# 4_5in_touch_LED_driver.net
KiCad netlist of a schematic drawn in EAGLE
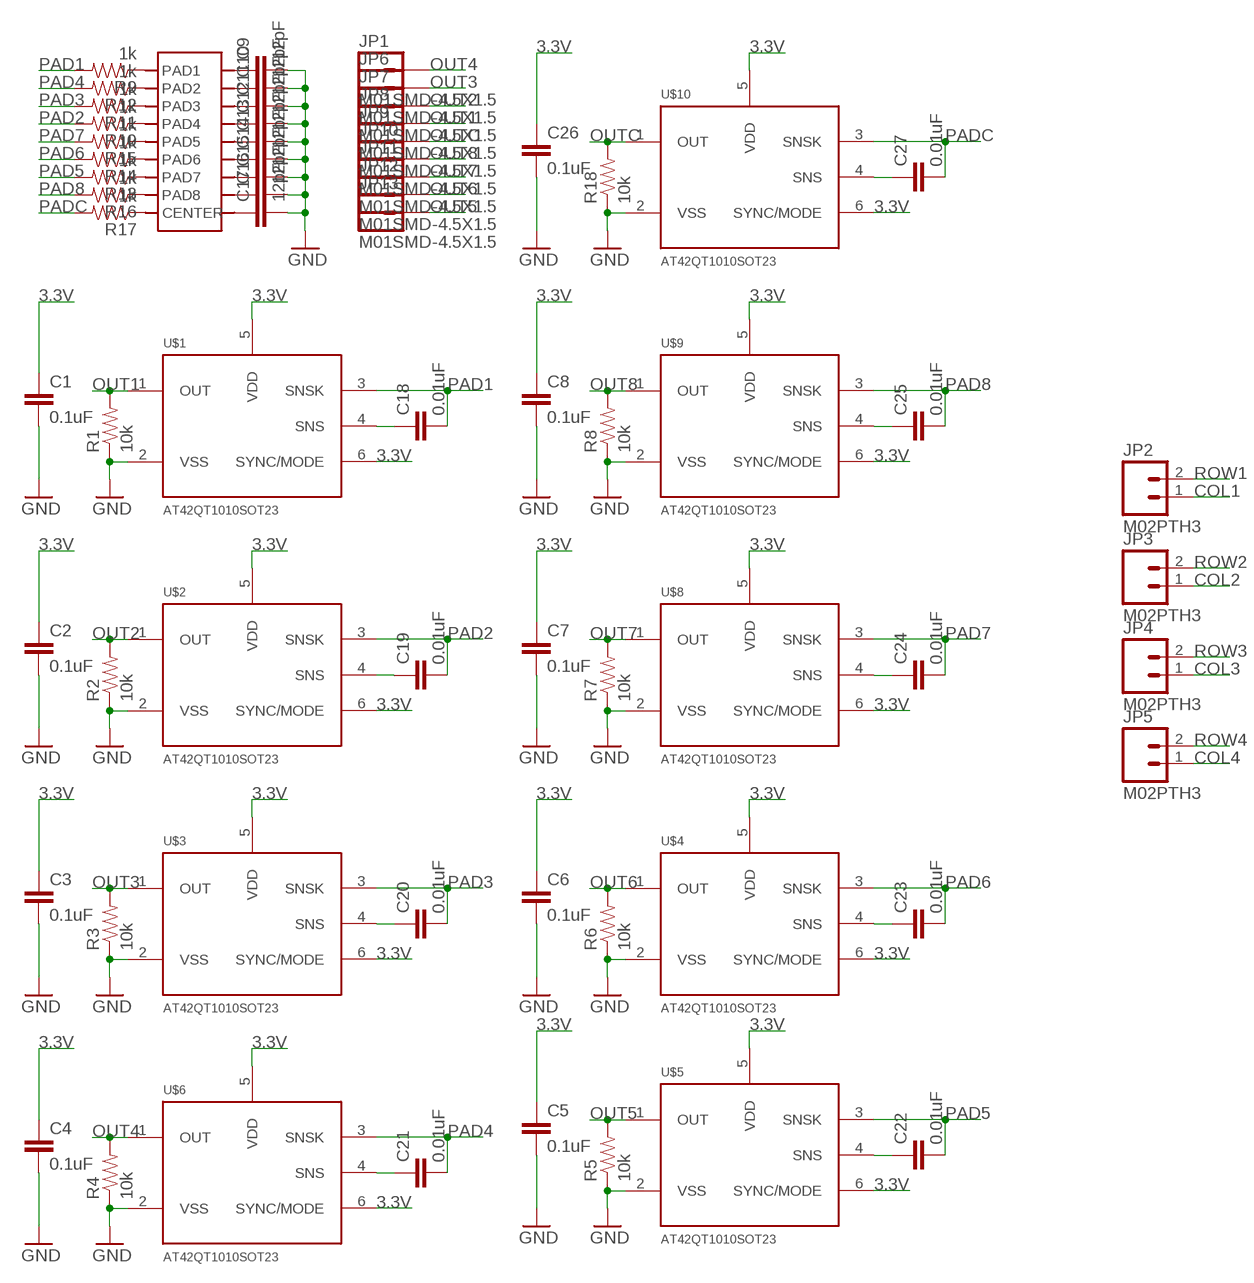
[diagram p0: schematic, sheet 1]

(export (version "E")
  (design (tool "Eeschema 10.0.6"))
  (components
    (comp (ref "C1")
      (value "0.1uF")
      (footprint "eagle-import:0603-CAP")
      (libsource (lib "eagle-import") (part "0.1UF-25V-5%(0603)"))
    )
    (comp (ref "C2")
      (value "0.1uF")
      (footprint "eagle-import:0603-CAP")
      (libsource (lib "eagle-import") (part "0.1UF-25V-5%(0603)"))
    )
    (comp (ref "C3")
      (value "0.1uF")
      (footprint "eagle-import:0603-CAP")
      (libsource (lib "eagle-import") (part "0.1UF-25V-5%(0603)"))
    )
    (comp (ref "C4")
      (value "0.1uF")
      (footprint "eagle-import:0603-CAP")
      (libsource (lib "eagle-import") (part "0.1UF-25V-5%(0603)"))
    )
    (comp (ref "C5")
      (value "0.1uF")
      (footprint "eagle-import:0603-CAP")
      (libsource (lib "eagle-import") (part "0.1UF-25V-5%(0603)"))
    )
    (comp (ref "C6")
      (value "0.1uF")
      (footprint "eagle-import:0603-CAP")
      (libsource (lib "eagle-import") (part "0.1UF-25V-5%(0603)"))
    )
    (comp (ref "C7")
      (value "0.1uF")
      (footprint "eagle-import:0603-CAP")
      (libsource (lib "eagle-import") (part "0.1UF-25V-5%(0603)"))
    )
    (comp (ref "C8")
      (value "0.1uF")
      (footprint "eagle-import:0603-CAP")
      (libsource (lib "eagle-import") (part "0.1UF-25V-5%(0603)"))
    )
    (comp (ref "C9")
      (value "12pF")
      (footprint "eagle-import:0805")
      (libsource (lib "eagle-import") (part "CAP0805"))
    )
    (comp (ref "C10")
      (value "12pF")
      (footprint "eagle-import:0805")
      (libsource (lib "eagle-import") (part "CAP0805"))
    )
    (comp (ref "C11")
      (value "12pF")
      (footprint "eagle-import:0805")
      (libsource (lib "eagle-import") (part "CAP0805"))
    )
    (comp (ref "C12")
      (value "12pF")
      (footprint "eagle-import:0805")
      (libsource (lib "eagle-import") (part "CAP0805"))
    )
    (comp (ref "C13")
      (value "12pF")
      (footprint "eagle-import:0805")
      (libsource (lib "eagle-import") (part "CAP0805"))
    )
    (comp (ref "C14")
      (value "12pF")
      (footprint "eagle-import:0805")
      (libsource (lib "eagle-import") (part "CAP0805"))
    )
    (comp (ref "C15")
      (value "12pF")
      (footprint "eagle-import:0805")
      (libsource (lib "eagle-import") (part "CAP0805"))
    )
    (comp (ref "C16")
      (value "12pF")
      (footprint "eagle-import:0805")
      (libsource (lib "eagle-import") (part "CAP0805"))
    )
    (comp (ref "C17")
      (value "12pF")
      (footprint "eagle-import:0805")
      (libsource (lib "eagle-import") (part "CAP0805"))
    )
    (comp (ref "C18")
      (value "0.01uF")
      (footprint "eagle-import:0805")
      (libsource (lib "eagle-import") (part "CAP0805"))
    )
    (comp (ref "C19")
      (value "0.01uF")
      (footprint "eagle-import:0805")
      (libsource (lib "eagle-import") (part "CAP0805"))
    )
    (comp (ref "C20")
      (value "0.01uF")
      (footprint "eagle-import:0805")
      (libsource (lib "eagle-import") (part "CAP0805"))
    )
    (comp (ref "C21")
      (value "0.01uF")
      (footprint "eagle-import:0805")
      (libsource (lib "eagle-import") (part "CAP0805"))
    )
    (comp (ref "C22")
      (value "0.01uF")
      (footprint "eagle-import:0805")
      (libsource (lib "eagle-import") (part "CAP0805"))
    )
    (comp (ref "C23")
      (value "0.01uF")
      (footprint "eagle-import:0805")
      (libsource (lib "eagle-import") (part "CAP0805"))
    )
    (comp (ref "C24")
      (value "0.01uF")
      (footprint "eagle-import:0805")
      (libsource (lib "eagle-import") (part "CAP0805"))
    )
    (comp (ref "C25")
      (value "0.01uF")
      (footprint "eagle-import:0805")
      (libsource (lib "eagle-import") (part "CAP0805"))
    )
    (comp (ref "C26")
      (value "0.1uF")
      (footprint "eagle-import:0603-CAP")
      (libsource (lib "eagle-import") (part "0.1UF-25V-5%(0603)"))
    )
    (comp (ref "C27")
      (value "0.01uF")
      (footprint "eagle-import:0805")
      (libsource (lib "eagle-import") (part "CAP0805"))
    )
    (comp (ref "JP1")
      (value "M01SMD-4.5X1.5")
      (footprint "eagle-import:PAD-1.5X4.5")
      (libsource (lib "eagle-import") (part "M01SMD-4.5X1.5"))
    )
    (comp (ref "JP2")
      (value "M02PTH3")
      (footprint "eagle-import:1X02_LONGPADS")
      (libsource (lib "eagle-import") (part "M02PTH3"))
    )
    (comp (ref "JP3")
      (value "M02PTH3")
      (footprint "eagle-import:1X02_LONGPADS")
      (libsource (lib "eagle-import") (part "M02PTH3"))
    )
    (comp (ref "JP4")
      (value "M02PTH3")
      (footprint "eagle-import:1X02_LONGPADS")
      (libsource (lib "eagle-import") (part "M02PTH3"))
    )
    (comp (ref "JP5")
      (value "M02PTH3")
      (footprint "eagle-import:1X02_LONGPADS")
      (libsource (lib "eagle-import") (part "M02PTH3"))
    )
    (comp (ref "JP6")
      (value "M01SMD-4.5X1.5")
      (footprint "eagle-import:PAD-1.5X4.5")
      (libsource (lib "eagle-import") (part "M01SMD-4.5X1.5"))
    )
    (comp (ref "JP7")
      (value "M01SMD-4.5X1.5")
      (footprint "eagle-import:PAD-1.5X4.5")
      (libsource (lib "eagle-import") (part "M01SMD-4.5X1.5"))
    )
    (comp (ref "JP8")
      (value "M01SMD-4.5X1.5")
      (footprint "eagle-import:PAD-1.5X4.5")
      (libsource (lib "eagle-import") (part "M01SMD-4.5X1.5"))
    )
    (comp (ref "JP9")
      (value "M01SMD-4.5X1.5")
      (footprint "eagle-import:PAD-1.5X4.5")
      (libsource (lib "eagle-import") (part "M01SMD-4.5X1.5"))
    )
    (comp (ref "JP10")
      (value "M01SMD-4.5X1.5")
      (footprint "eagle-import:PAD-1.5X4.5")
      (libsource (lib "eagle-import") (part "M01SMD-4.5X1.5"))
    )
    (comp (ref "JP11")
      (value "M01SMD-4.5X1.5")
      (footprint "eagle-import:PAD-1.5X4.5")
      (libsource (lib "eagle-import") (part "M01SMD-4.5X1.5"))
    )
    (comp (ref "JP12")
      (value "M01SMD-4.5X1.5")
      (footprint "eagle-import:PAD-1.5X4.5")
      (libsource (lib "eagle-import") (part "M01SMD-4.5X1.5"))
    )
    (comp (ref "JP13")
      (value "M01SMD-4.5X1.5")
      (footprint "eagle-import:PAD-1.5X4.5")
      (libsource (lib "eagle-import") (part "M01SMD-4.5X1.5"))
    )
    (comp (ref "R1")
      (value "10k")
      (footprint "eagle-import:0603-RES")
      (libsource (lib "eagle-import") (part "RESISTOR0603"))
    )
    (comp (ref "R2")
      (value "10k")
      (footprint "eagle-import:0603-RES")
      (libsource (lib "eagle-import") (part "RESISTOR0603"))
    )
    (comp (ref "R3")
      (value "10k")
      (footprint "eagle-import:0603-RES")
      (libsource (lib "eagle-import") (part "RESISTOR0603"))
    )
    (comp (ref "R4")
      (value "10k")
      (footprint "eagle-import:0603-RES")
      (libsource (lib "eagle-import") (part "RESISTOR0603"))
    )
    (comp (ref "R5")
      (value "10k")
      (footprint "eagle-import:0603-RES")
      (libsource (lib "eagle-import") (part "RESISTOR0603"))
    )
    (comp (ref "R6")
      (value "10k")
      (footprint "eagle-import:0603-RES")
      (libsource (lib "eagle-import") (part "RESISTOR0603"))
    )
    (comp (ref "R7")
      (value "10k")
      (footprint "eagle-import:0603-RES")
      (libsource (lib "eagle-import") (part "RESISTOR0603"))
    )
    (comp (ref "R8")
      (value "10k")
      (footprint "eagle-import:0603-RES")
      (libsource (lib "eagle-import") (part "RESISTOR0603"))
    )
    (comp (ref "R9")
      (value "1k")
      (footprint "eagle-import:0603-RES")
      (libsource (lib "eagle-import") (part "RESISTOR0603"))
    )
    (comp (ref "R10")
      (value "1k")
      (footprint "eagle-import:0603-RES")
      (libsource (lib "eagle-import") (part "RESISTOR0603"))
    )
    (comp (ref "R11")
      (value "1k")
      (footprint "eagle-import:0603-RES")
      (libsource (lib "eagle-import") (part "RESISTOR0603"))
    )
    (comp (ref "R12")
      (value "1k")
      (footprint "eagle-import:0603-RES")
      (libsource (lib "eagle-import") (part "RESISTOR0603"))
    )
    (comp (ref "R13")
      (value "1k")
      (footprint "eagle-import:0603-RES")
      (libsource (lib "eagle-import") (part "RESISTOR0603"))
    )
    (comp (ref "R14")
      (value "1k")
      (footprint "eagle-import:0603-RES")
      (libsource (lib "eagle-import") (part "RESISTOR0603"))
    )
    (comp (ref "R15")
      (value "1k")
      (footprint "eagle-import:0603-RES")
      (libsource (lib "eagle-import") (part "RESISTOR0603"))
    )
    (comp (ref "R16")
      (value "1k")
      (footprint "eagle-import:0603-RES")
      (libsource (lib "eagle-import") (part "RESISTOR0603"))
    )
    (comp (ref "R17")
      (value "1k")
      (footprint "eagle-import:0603-RES")
      (libsource (lib "eagle-import") (part "RESISTOR0603"))
    )
    (comp (ref "R18")
      (value "10k")
      (footprint "eagle-import:0603-RES")
      (libsource (lib "eagle-import") (part "RESISTOR0603"))
    )
    (comp (ref "U$1")
      (value "AT42QT1010SOT23")
      (footprint "eagle-import:SOT23-6")
      (libsource (lib "eagle-import") (part "AT42QT1010SOT23"))
    )
    (comp (ref "U$2")
      (value "AT42QT1010SOT23")
      (footprint "eagle-import:SOT23-6")
      (libsource (lib "eagle-import") (part "AT42QT1010SOT23"))
    )
    (comp (ref "U$3")
      (value "AT42QT1010SOT23")
      (footprint "eagle-import:SOT23-6")
      (libsource (lib "eagle-import") (part "AT42QT1010SOT23"))
    )
    (comp (ref "U$4")
      (value "AT42QT1010SOT23")
      (footprint "eagle-import:SOT23-6")
      (libsource (lib "eagle-import") (part "AT42QT1010SOT23"))
    )
    (comp (ref "U$5")
      (value "AT42QT1010SOT23")
      (footprint "eagle-import:SOT23-6")
      (libsource (lib "eagle-import") (part "AT42QT1010SOT23"))
    )
    (comp (ref "U$6")
      (value "AT42QT1010SOT23")
      (footprint "eagle-import:SOT23-6")
      (libsource (lib "eagle-import") (part "AT42QT1010SOT23"))
    )
    (comp (ref "U$7")
      (value "9_PAD_TOUCH4IN")
      (footprint "eagle-import:4IN_TOUCH_PAD")
      (libsource (lib "eagle-import") (part "9_PAD_TOUCH4IN"))
    )
    (comp (ref "U$8")
      (value "AT42QT1010SOT23")
      (footprint "eagle-import:SOT23-6")
      (libsource (lib "eagle-import") (part "AT42QT1010SOT23"))
    )
    (comp (ref "U$9")
      (value "AT42QT1010SOT23")
      (footprint "eagle-import:SOT23-6")
      (libsource (lib "eagle-import") (part "AT42QT1010SOT23"))
    )
    (comp (ref "U$10")
      (value "AT42QT1010SOT23")
      (footprint "eagle-import:SOT23-6")
      (libsource (lib "eagle-import") (part "AT42QT1010SOT23"))
    )
  )
  (nets
    (net (code "1") (name "/3.3V") (class "Default")
      (node (ref "C1") (pin "1") (pinfunction "1_1") (pintype "passive"))
      (node (ref "C2") (pin "1") (pinfunction "1_1") (pintype "passive"))
      (node (ref "C26") (pin "1") (pinfunction "1_1") (pintype "passive"))
      (node (ref "C3") (pin "1") (pinfunction "1_1") (pintype "passive"))
      (node (ref "C4") (pin "1") (pinfunction "1_1") (pintype "passive"))
      (node (ref "C5") (pin "1") (pinfunction "1_1") (pintype "passive"))
      (node (ref "C6") (pin "1") (pinfunction "1_1") (pintype "passive"))
      (node (ref "C7") (pin "1") (pinfunction "1_1") (pintype "passive"))
      (node (ref "C8") (pin "1") (pinfunction "1_1") (pintype "passive"))
      (node (ref "U$1") (pin "5") (pinfunction "VDD_5") (pintype "bidirectional"))
      (node (ref "U$1") (pin "6") (pinfunction "SYNC/MODE_6") (pintype "bidirectional"))
      (node (ref "U$10") (pin "5") (pinfunction "VDD_5") (pintype "bidirectional"))
      (node (ref "U$10") (pin "6") (pinfunction "SYNC/MODE_6") (pintype "bidirectional"))
      (node (ref "U$2") (pin "5") (pinfunction "VDD_5") (pintype "bidirectional"))
      (node (ref "U$2") (pin "6") (pinfunction "SYNC/MODE_6") (pintype "bidirectional"))
      (node (ref "U$3") (pin "5") (pinfunction "VDD_5") (pintype "bidirectional"))
      (node (ref "U$3") (pin "6") (pinfunction "SYNC/MODE_6") (pintype "bidirectional"))
      (node (ref "U$4") (pin "5") (pinfunction "VDD_5") (pintype "bidirectional"))
      (node (ref "U$4") (pin "6") (pinfunction "SYNC/MODE_6") (pintype "bidirectional"))
      (node (ref "U$5") (pin "5") (pinfunction "VDD_5") (pintype "bidirectional"))
      (node (ref "U$5") (pin "6") (pinfunction "SYNC/MODE_6") (pintype "bidirectional"))
      (node (ref "U$6") (pin "5") (pinfunction "VDD_5") (pintype "bidirectional"))
      (node (ref "U$6") (pin "6") (pinfunction "SYNC/MODE_6") (pintype "bidirectional"))
      (node (ref "U$8") (pin "5") (pinfunction "VDD_5") (pintype "bidirectional"))
      (node (ref "U$8") (pin "6") (pinfunction "SYNC/MODE_6") (pintype "bidirectional"))
      (node (ref "U$9") (pin "5") (pinfunction "VDD_5") (pintype "bidirectional"))
      (node (ref "U$9") (pin "6") (pinfunction "SYNC/MODE_6") (pintype "bidirectional"))
    )
    (net (code "2") (name "/COL1") (class "Default")
      (node (ref "JP2") (pin "1") (pinfunction "1_1") (pintype "passive"))
    )
    (net (code "3") (name "/COL2") (class "Default")
      (node (ref "JP3") (pin "1") (pinfunction "1_1") (pintype "passive"))
    )
    (net (code "4") (name "/COL3") (class "Default")
      (node (ref "JP4") (pin "1") (pinfunction "1_1") (pintype "passive"))
    )
    (net (code "5") (name "/COL4") (class "Default")
      (node (ref "JP5") (pin "1") (pinfunction "1_1") (pintype "passive"))
    )
    (net (code "6") (name "/OUT1") (class "Default")
      (node (ref "JP8") (pin "P$1") (pinfunction "1_P$1") (pintype "passive"))
      (node (ref "R1") (pin "2") (pinfunction "2_2") (pintype "passive"))
      (node (ref "U$1") (pin "1") (pinfunction "OUT_1") (pintype "bidirectional"))
    )
    (net (code "7") (name "/OUT2") (class "Default")
      (node (ref "JP7") (pin "P$1") (pinfunction "1_P$1") (pintype "passive"))
      (node (ref "R2") (pin "2") (pinfunction "2_2") (pintype "passive"))
      (node (ref "U$2") (pin "1") (pinfunction "OUT_1") (pintype "bidirectional"))
    )
    (net (code "8") (name "/OUT3") (class "Default")
      (node (ref "JP6") (pin "P$1") (pinfunction "1_P$1") (pintype "passive"))
      (node (ref "R3") (pin "2") (pinfunction "2_2") (pintype "passive"))
      (node (ref "U$3") (pin "1") (pinfunction "OUT_1") (pintype "bidirectional"))
    )
    (net (code "9") (name "/OUT4") (class "Default")
      (node (ref "JP1") (pin "P$1") (pinfunction "1_P$1") (pintype "passive"))
      (node (ref "R4") (pin "2") (pinfunction "2_2") (pintype "passive"))
      (node (ref "U$6") (pin "1") (pinfunction "OUT_1") (pintype "bidirectional"))
    )
    (net (code "10") (name "/OUT5") (class "Default")
      (node (ref "JP13") (pin "P$1") (pinfunction "1_P$1") (pintype "passive"))
      (node (ref "R5") (pin "2") (pinfunction "2_2") (pintype "passive"))
      (node (ref "U$5") (pin "1") (pinfunction "OUT_1") (pintype "bidirectional"))
    )
    (net (code "11") (name "/OUT6") (class "Default")
      (node (ref "JP12") (pin "P$1") (pinfunction "1_P$1") (pintype "passive"))
      (node (ref "R6") (pin "2") (pinfunction "2_2") (pintype "passive"))
      (node (ref "U$4") (pin "1") (pinfunction "OUT_1") (pintype "bidirectional"))
    )
    (net (code "12") (name "/OUT7") (class "Default")
      (node (ref "JP11") (pin "P$1") (pinfunction "1_P$1") (pintype "passive"))
      (node (ref "R7") (pin "2") (pinfunction "2_2") (pintype "passive"))
      (node (ref "U$8") (pin "1") (pinfunction "OUT_1") (pintype "bidirectional"))
    )
    (net (code "13") (name "/OUT8") (class "Default")
      (node (ref "JP10") (pin "P$1") (pinfunction "1_P$1") (pintype "passive"))
      (node (ref "R8") (pin "2") (pinfunction "2_2") (pintype "passive"))
      (node (ref "U$9") (pin "1") (pinfunction "OUT_1") (pintype "bidirectional"))
    )
    (net (code "14") (name "/OUTC") (class "Default")
      (node (ref "JP9") (pin "P$1") (pinfunction "1_P$1") (pintype "passive"))
      (node (ref "R18") (pin "2") (pinfunction "2_2") (pintype "passive"))
      (node (ref "U$10") (pin "1") (pinfunction "OUT_1") (pintype "bidirectional"))
    )
    (net (code "15") (name "/PAD1") (class "Default")
      (node (ref "C18") (pin "2") (pinfunction "2_2") (pintype "passive"))
      (node (ref "R9") (pin "2") (pinfunction "2_2") (pintype "passive"))
      (node (ref "U$1") (pin "3") (pinfunction "SNSK_3") (pintype "bidirectional"))
    )
    (net (code "16") (name "/PAD2") (class "Default")
      (node (ref "C19") (pin "2") (pinfunction "2_2") (pintype "passive"))
      (node (ref "R10") (pin "2") (pinfunction "2_2") (pintype "passive"))
      (node (ref "U$2") (pin "3") (pinfunction "SNSK_3") (pintype "bidirectional"))
    )
    (net (code "17") (name "/PAD3") (class "Default")
      (node (ref "C20") (pin "2") (pinfunction "2_2") (pintype "passive"))
      (node (ref "R11") (pin "2") (pinfunction "2_2") (pintype "passive"))
      (node (ref "U$3") (pin "3") (pinfunction "SNSK_3") (pintype "bidirectional"))
    )
    (net (code "18") (name "/PAD4") (class "Default")
      (node (ref "C21") (pin "2") (pinfunction "2_2") (pintype "passive"))
      (node (ref "R12") (pin "2") (pinfunction "2_2") (pintype "passive"))
      (node (ref "U$6") (pin "3") (pinfunction "SNSK_3") (pintype "bidirectional"))
    )
    (net (code "19") (name "/PAD5") (class "Default")
      (node (ref "C22") (pin "2") (pinfunction "2_2") (pintype "passive"))
      (node (ref "R13") (pin "2") (pinfunction "2_2") (pintype "passive"))
      (node (ref "U$5") (pin "3") (pinfunction "SNSK_3") (pintype "bidirectional"))
    )
    (net (code "20") (name "/PAD6") (class "Default")
      (node (ref "C23") (pin "2") (pinfunction "2_2") (pintype "passive"))
      (node (ref "R14") (pin "2") (pinfunction "2_2") (pintype "passive"))
      (node (ref "U$4") (pin "3") (pinfunction "SNSK_3") (pintype "bidirectional"))
    )
    (net (code "21") (name "/PAD7") (class "Default")
      (node (ref "C24") (pin "2") (pinfunction "2_2") (pintype "passive"))
      (node (ref "R15") (pin "2") (pinfunction "2_2") (pintype "passive"))
      (node (ref "U$8") (pin "3") (pinfunction "SNSK_3") (pintype "bidirectional"))
    )
    (net (code "22") (name "/PAD8") (class "Default")
      (node (ref "C25") (pin "2") (pinfunction "2_2") (pintype "passive"))
      (node (ref "R16") (pin "2") (pinfunction "2_2") (pintype "passive"))
      (node (ref "U$9") (pin "3") (pinfunction "SNSK_3") (pintype "bidirectional"))
    )
    (net (code "23") (name "/PADC") (class "Default")
      (node (ref "C27") (pin "2") (pinfunction "2_2") (pintype "passive"))
      (node (ref "R17") (pin "2") (pinfunction "2_2") (pintype "passive"))
      (node (ref "U$10") (pin "3") (pinfunction "SNSK_3") (pintype "bidirectional"))
    )
    (net (code "24") (name "/ROW1") (class "Default")
      (node (ref "JP2") (pin "2") (pinfunction "2_2") (pintype "passive"))
    )
    (net (code "25") (name "/ROW2") (class "Default")
      (node (ref "JP3") (pin "2") (pinfunction "2_2") (pintype "passive"))
    )
    (net (code "26") (name "/ROW3") (class "Default")
      (node (ref "JP4") (pin "2") (pinfunction "2_2") (pintype "passive"))
    )
    (net (code "27") (name "/ROW4") (class "Default")
      (node (ref "JP5") (pin "2") (pinfunction "2_2") (pintype "passive"))
    )
    (net (code "28") (name "GND") (class "Default")
      (node (ref "C1") (pin "2") (pinfunction "2_2") (pintype "passive"))
      (node (ref "C10") (pin "2") (pinfunction "2_2") (pintype "passive"))
      (node (ref "C11") (pin "2") (pinfunction "2_2") (pintype "passive"))
      (node (ref "C12") (pin "2") (pinfunction "2_2") (pintype "passive"))
      (node (ref "C13") (pin "2") (pinfunction "2_2") (pintype "passive"))
      (node (ref "C14") (pin "2") (pinfunction "2_2") (pintype "passive"))
      (node (ref "C15") (pin "2") (pinfunction "2_2") (pintype "passive"))
      (node (ref "C16") (pin "2") (pinfunction "2_2") (pintype "passive"))
      (node (ref "C17") (pin "2") (pinfunction "2_2") (pintype "passive"))
      (node (ref "C2") (pin "2") (pinfunction "2_2") (pintype "passive"))
      (node (ref "C26") (pin "2") (pinfunction "2_2") (pintype "passive"))
      (node (ref "C3") (pin "2") (pinfunction "2_2") (pintype "passive"))
      (node (ref "C4") (pin "2") (pinfunction "2_2") (pintype "passive"))
      (node (ref "C5") (pin "2") (pinfunction "2_2") (pintype "passive"))
      (node (ref "C6") (pin "2") (pinfunction "2_2") (pintype "passive"))
      (node (ref "C7") (pin "2") (pinfunction "2_2") (pintype "passive"))
      (node (ref "C8") (pin "2") (pinfunction "2_2") (pintype "passive"))
      (node (ref "C9") (pin "2") (pinfunction "2_2") (pintype "passive"))
      (node (ref "R1") (pin "1") (pinfunction "1_1") (pintype "passive"))
      (node (ref "R18") (pin "1") (pinfunction "1_1") (pintype "passive"))
      (node (ref "R2") (pin "1") (pinfunction "1_1") (pintype "passive"))
      (node (ref "R3") (pin "1") (pinfunction "1_1") (pintype "passive"))
      (node (ref "R4") (pin "1") (pinfunction "1_1") (pintype "passive"))
      (node (ref "R5") (pin "1") (pinfunction "1_1") (pintype "passive"))
      (node (ref "R6") (pin "1") (pinfunction "1_1") (pintype "passive"))
      (node (ref "R7") (pin "1") (pinfunction "1_1") (pintype "passive"))
      (node (ref "R8") (pin "1") (pinfunction "1_1") (pintype "passive"))
      (node (ref "U$1") (pin "2") (pinfunction "VSS_2") (pintype "bidirectional"))
      (node (ref "U$10") (pin "2") (pinfunction "VSS_2") (pintype "bidirectional"))
      (node (ref "U$2") (pin "2") (pinfunction "VSS_2") (pintype "bidirectional"))
      (node (ref "U$3") (pin "2") (pinfunction "VSS_2") (pintype "bidirectional"))
      (node (ref "U$4") (pin "2") (pinfunction "VSS_2") (pintype "bidirectional"))
      (node (ref "U$5") (pin "2") (pinfunction "VSS_2") (pintype "bidirectional"))
      (node (ref "U$6") (pin "2") (pinfunction "VSS_2") (pintype "bidirectional"))
      (node (ref "U$8") (pin "2") (pinfunction "VSS_2") (pintype "bidirectional"))
      (node (ref "U$9") (pin "2") (pinfunction "VSS_2") (pintype "bidirectional"))
    )
    (net (code "29") (name "Net-(C9-Pad1)") (class "Default")
      (node (ref "C9") (pin "1") (pinfunction "1_1") (pintype "passive"))
      (node (ref "U$7") (pin "P$10") (pinfunction "P$10_P$10") (pintype "bidirectional"))
    )
    (net (code "30") (name "Net-(C10-Pad1)") (class "Default")
      (node (ref "C10") (pin "1") (pinfunction "1_1") (pintype "passive"))
      (node (ref "U$7") (pin "P$11") (pinfunction "P$11_P$11") (pintype "bidirectional"))
    )
    (net (code "31") (name "Net-(C11-Pad1)") (class "Default")
      (node (ref "C11") (pin "1") (pinfunction "1_1") (pintype "passive"))
      (node (ref "U$7") (pin "P$12") (pinfunction "P$12_P$12") (pintype "bidirectional"))
    )
    (net (code "32") (name "Net-(C12-Pad1)") (class "Default")
      (node (ref "C12") (pin "1") (pinfunction "1_1") (pintype "passive"))
      (node (ref "U$7") (pin "P$13") (pinfunction "P$13_P$13") (pintype "bidirectional"))
    )
    (net (code "33") (name "Net-(C13-Pad1)") (class "Default")
      (node (ref "C13") (pin "1") (pinfunction "1_1") (pintype "passive"))
      (node (ref "U$7") (pin "P$14") (pinfunction "P$14_P$14") (pintype "bidirectional"))
    )
    (net (code "34") (name "Net-(C14-Pad1)") (class "Default")
      (node (ref "C14") (pin "1") (pinfunction "1_1") (pintype "passive"))
      (node (ref "U$7") (pin "P$15") (pinfunction "P$15_P$15") (pintype "bidirectional"))
    )
    (net (code "35") (name "Net-(C15-Pad1)") (class "Default")
      (node (ref "C15") (pin "1") (pinfunction "1_1") (pintype "passive"))
      (node (ref "U$7") (pin "P$16") (pinfunction "P$16_P$16") (pintype "bidirectional"))
    )
    (net (code "36") (name "Net-(C16-Pad1)") (class "Default")
      (node (ref "C16") (pin "1") (pinfunction "1_1") (pintype "passive"))
      (node (ref "U$7") (pin "P$17") (pinfunction "P$17_P$17") (pintype "bidirectional"))
    )
    (net (code "37") (name "Net-(C17-Pad1)") (class "Default")
      (node (ref "C17") (pin "1") (pinfunction "1_1") (pintype "passive"))
      (node (ref "U$7") (pin "P$18") (pinfunction "P$18_P$18") (pintype "bidirectional"))
    )
    (net (code "38") (name "Net-(U$1-SNS)") (class "Default")
      (node (ref "C18") (pin "1") (pinfunction "1_1") (pintype "passive"))
      (node (ref "U$1") (pin "4") (pinfunction "SNS_4") (pintype "bidirectional"))
    )
    (net (code "39") (name "Net-(U$2-SNS)") (class "Default")
      (node (ref "C19") (pin "1") (pinfunction "1_1") (pintype "passive"))
      (node (ref "U$2") (pin "4") (pinfunction "SNS_4") (pintype "bidirectional"))
    )
    (net (code "40") (name "Net-(U$3-SNS)") (class "Default")
      (node (ref "C20") (pin "1") (pinfunction "1_1") (pintype "passive"))
      (node (ref "U$3") (pin "4") (pinfunction "SNS_4") (pintype "bidirectional"))
    )
    (net (code "41") (name "Net-(U$4-SNS)") (class "Default")
      (node (ref "C23") (pin "1") (pinfunction "1_1") (pintype "passive"))
      (node (ref "U$4") (pin "4") (pinfunction "SNS_4") (pintype "bidirectional"))
    )
    (net (code "42") (name "Net-(U$5-SNS)") (class "Default")
      (node (ref "C22") (pin "1") (pinfunction "1_1") (pintype "passive"))
      (node (ref "U$5") (pin "4") (pinfunction "SNS_4") (pintype "bidirectional"))
    )
    (net (code "43") (name "Net-(U$6-SNS)") (class "Default")
      (node (ref "C21") (pin "1") (pinfunction "1_1") (pintype "passive"))
      (node (ref "U$6") (pin "4") (pinfunction "SNS_4") (pintype "bidirectional"))
    )
    (net (code "44") (name "Net-(U$7-CENTER)") (class "Default")
      (node (ref "R17") (pin "1") (pinfunction "1_1") (pintype "passive"))
      (node (ref "U$7") (pin "P$9") (pinfunction "CENTER_P$9") (pintype "bidirectional"))
    )
    (net (code "45") (name "Net-(U$7-PAD1)") (class "Default")
      (node (ref "R9") (pin "1") (pinfunction "1_1") (pintype "passive"))
      (node (ref "U$7") (pin "P$1") (pinfunction "PAD1_P$1") (pintype "bidirectional"))
    )
    (net (code "46") (name "Net-(U$7-PAD2)") (class "Default")
      (node (ref "R12") (pin "1") (pinfunction "1_1") (pintype "passive"))
      (node (ref "U$7") (pin "P$2") (pinfunction "PAD2_P$2") (pintype "bidirectional"))
    )
    (net (code "47") (name "Net-(U$7-PAD3)") (class "Default")
      (node (ref "R11") (pin "1") (pinfunction "1_1") (pintype "passive"))
      (node (ref "U$7") (pin "P$3") (pinfunction "PAD3_P$3") (pintype "bidirectional"))
    )
    (net (code "48") (name "Net-(U$7-PAD4)") (class "Default")
      (node (ref "R10") (pin "1") (pinfunction "1_1") (pintype "passive"))
      (node (ref "U$7") (pin "P$4") (pinfunction "PAD4_P$4") (pintype "bidirectional"))
    )
    (net (code "49") (name "Net-(U$7-PAD5)") (class "Default")
      (node (ref "R15") (pin "1") (pinfunction "1_1") (pintype "passive"))
      (node (ref "U$7") (pin "P$5") (pinfunction "PAD5_P$5") (pintype "bidirectional"))
    )
    (net (code "50") (name "Net-(U$7-PAD6)") (class "Default")
      (node (ref "R14") (pin "1") (pinfunction "1_1") (pintype "passive"))
      (node (ref "U$7") (pin "P$6") (pinfunction "PAD6_P$6") (pintype "bidirectional"))
    )
    (net (code "51") (name "Net-(U$7-PAD7)") (class "Default")
      (node (ref "R13") (pin "1") (pinfunction "1_1") (pintype "passive"))
      (node (ref "U$7") (pin "P$7") (pinfunction "PAD7_P$7") (pintype "bidirectional"))
    )
    (net (code "52") (name "Net-(U$7-PAD8)") (class "Default")
      (node (ref "R16") (pin "1") (pinfunction "1_1") (pintype "passive"))
      (node (ref "U$7") (pin "P$8") (pinfunction "PAD8_P$8") (pintype "bidirectional"))
    )
    (net (code "53") (name "Net-(U$8-SNS)") (class "Default")
      (node (ref "C24") (pin "1") (pinfunction "1_1") (pintype "passive"))
      (node (ref "U$8") (pin "4") (pinfunction "SNS_4") (pintype "bidirectional"))
    )
    (net (code "54") (name "Net-(U$9-SNS)") (class "Default")
      (node (ref "C25") (pin "1") (pinfunction "1_1") (pintype "passive"))
      (node (ref "U$9") (pin "4") (pinfunction "SNS_4") (pintype "bidirectional"))
    )
    (net (code "55") (name "Net-(U$10-SNS)") (class "Default")
      (node (ref "C27") (pin "1") (pinfunction "1_1") (pintype "passive"))
      (node (ref "U$10") (pin "4") (pinfunction "SNS_4") (pintype "bidirectional"))
    )
  )
)
